# CoaxPress_SFP.net
KiCad netlist of a schematic drawn in Altium Designer
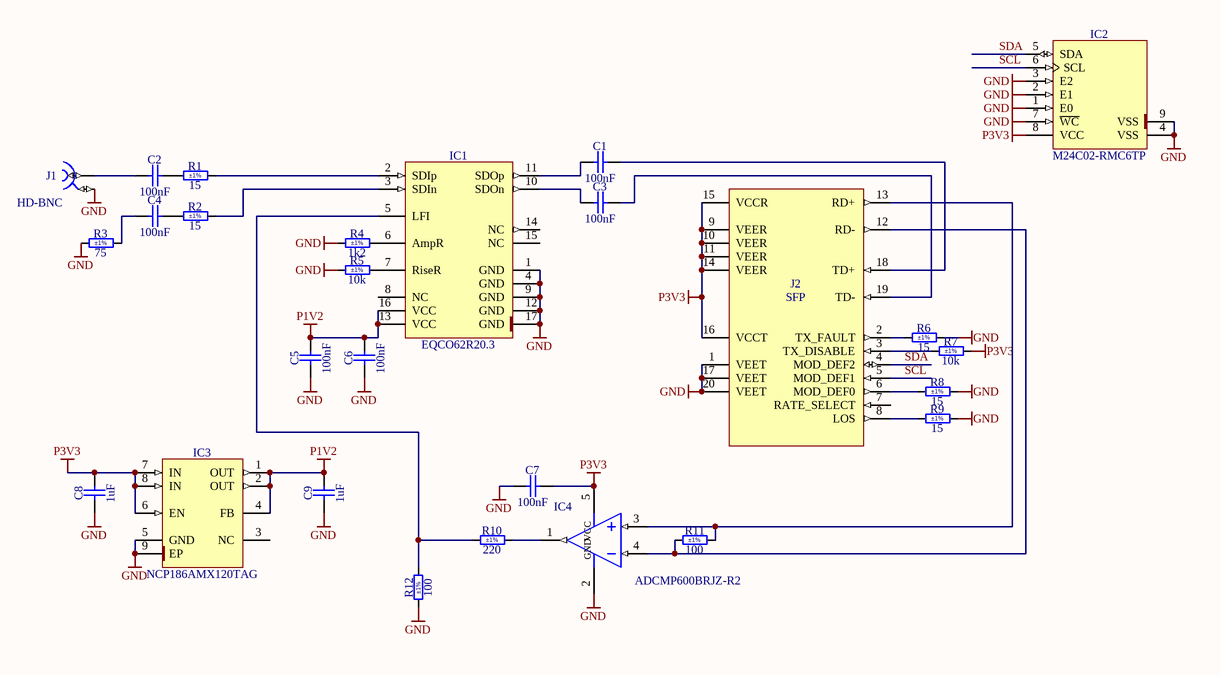
[diagram p0: CoaxPress_SFP.SchDoc]

(export (version "E")
  (design (tool "Eeschema 10.0.6"))
  (components
    (comp (ref "C1")
      (value "100nF")
      (footprint "CAPC1005X55N")
      (description "Non-polarised capacitor")
      (fields
        (field (name "PART NUMBER") "CC0402_100NF_16V_10%_X5R")
        (field (name "VOLTAGE") "16V")
        (field (name "AUTHOR") "CERN DEM JLC")
      )
      (libsource (lib "Capacitors") (part "Capacitor - non polarized"))
    )
    (comp (ref "C2")
      (value "100nF")
      (footprint "CAPC1005X55N")
      (description "Non-polarised capacitor")
      (fields
        (field (name "PART NUMBER") "CC0402_100NF_16V_10%_X5R")
        (field (name "VOLTAGE") "16V")
        (field (name "AUTHOR") "CERN DEM JLC")
      )
      (libsource (lib "Capacitors") (part "Capacitor - non polarized"))
    )
    (comp (ref "C3")
      (value "100nF")
      (footprint "CAPC1005X55N")
      (description "Non-polarised capacitor")
      (fields
        (field (name "PART NUMBER") "CC0402_100NF_16V_10%_X5R")
        (field (name "VOLTAGE") "16V")
        (field (name "AUTHOR") "CERN DEM JLC")
      )
      (libsource (lib "Capacitors") (part "Capacitor - non polarized"))
    )
    (comp (ref "C4")
      (value "100nF")
      (footprint "CAPC1005X55N")
      (description "Non-polarised capacitor")
      (fields
        (field (name "PART NUMBER") "CC0402_100NF_16V_10%_X5R")
        (field (name "VOLTAGE") "16V")
        (field (name "AUTHOR") "CERN DEM JLC")
      )
      (libsource (lib "Capacitors") (part "Capacitor - non polarized"))
    )
    (comp (ref "C5")
      (value "100nF")
      (footprint "CAPC1005X55N")
      (description "Non-polarised capacitor")
      (fields
        (field (name "PART NUMBER") "CC0402_100NF_16V_10%_X5R")
        (field (name "VOLTAGE") "16V")
        (field (name "AUTHOR") "CERN DEM JLC")
      )
      (libsource (lib "Capacitors") (part "Capacitor - non polarized"))
    )
    (comp (ref "C6")
      (value "100nF")
      (footprint "CAPC1005X55N")
      (description "Non-polarised capacitor")
      (fields
        (field (name "PART NUMBER") "CC0402_100NF_16V_10%_X5R")
        (field (name "VOLTAGE") "16V")
        (field (name "AUTHOR") "CERN DEM JLC")
      )
      (libsource (lib "Capacitors") (part "Capacitor - non polarized"))
    )
    (comp (ref "C7")
      (value "100nF")
      (footprint "CAPC1005X55N")
      (description "Non-polarised capacitor")
      (fields
        (field (name "PART NUMBER") "CC0402_100NF_16V_10%_X5R")
        (field (name "VOLTAGE") "16V")
        (field (name "AUTHOR") "CERN DEM JLC")
      )
      (libsource (lib "Capacitors") (part "Capacitor - non polarized"))
    )
    (comp (ref "C8")
      (value "1uF")
      (footprint "CAPC1005X55N")
      (description "Non-polarised capacitor")
      (fields
        (field (name "PART NUMBER") "CC0402_1UF_16V_10%_X5R")
        (field (name "VOLTAGE") "16V")
        (field (name "AUTHOR") "CERN DEM JLC")
      )
      (libsource (lib "Capacitors") (part "Capacitor - non polarized"))
    )
    (comp (ref "C9")
      (value "1uF")
      (footprint "CAPC1005X55N")
      (description "Non-polarised capacitor")
      (fields
        (field (name "PART NUMBER") "CC0402_1UF_16V_10%_X5R")
        (field (name "VOLTAGE") "16V")
        (field (name "AUTHOR") "CERN DEM JLC")
      )
      (libsource (lib "Capacitors") (part "Capacitor - non polarized"))
    )
    (comp (ref "IC1")
      (value "EQCO62R20.3")
      (footprint "QFN65P400X400X95-17N-S215")
      (description "6.25Gbps Asymmetric Coax Equalizer")
      (fields (field (name "MANUFACTURER") "MICROCHIP TECHNOLOGY") (field (name "AUTHOR") "CERN DEM JLC"))
      (libsource (lib "ICs And Semiconductors") (part "EQCO62R20"))
    )
    (comp (ref "IC2")
      (value "M24C02-RMC6TP")
      (footprint "SON50P300X200X60-9N-S160")
      (description "2-Kbit (256 x 8bit) Serial I2C Bus EEPROM")
      (fields (field (name "MANUFACTURER") "ST MICROELECTRONICS") (field (name "AUTHOR") "CERN DEM MR"))
      (libsource (lib "ICs And Semiconductors") (part "M24C02-RMC"))
    )
    (comp (ref "IC3")
      (value "NCP186AMX120TAG")
      (footprint "ONSEMI_CASE 711AS")
      (description "1A, LDO Regulator - Fast Transient Response Low Voltage")
      (fields
        (field (name "MANUFACTURER") "ON SEMICONDUCTOR")
        (field (name "MANUFACTURER PART NUMBER") "NCP186AMX120TA")
        (field (name "AUTHOR") "CERN DEM BC")
      )
      (libsource (lib "ICs And Semiconductors") (part "NCP186AMX"))
    )
    (comp (ref "IC4")
      (value "ADCMP600BRJZ-R2")
      (footprint "SOT95P280X145-5N")
      (description "Rail-to-Rail, Very Fast, 2.5 V to 5.5 V Single-Supply TTL/CMOS Comparator")
      (fields
        (field (name "MANUFACTURER") "ANALOG DEVICES")
        (field (name "MANUFACTURER PART NUMBER") "ADCMP600BRJ")
        (field (name "AUTHOR") "CERN DEM JLC")
      )
      (libsource (lib "ICs And Semiconductors") (part "ADCMP600"))
    )
    (comp (ref "J1")
      (value "HD-BNC")
      (footprint "AMPHENOL_34-1030-12G")
      (fields
        (field (name "PART NUMBER") "AMPHENOL_34-1030-12G")
        (field (name "MANUFACTURER") "AMPHENOL-RF")
        (field (name "MANUFACTURER PART NUMBER") "34-1030-12G")
        (field (name "AUTHOR") "CERN DEM JLC")
      )
      (libsource (lib "Connectors") (part "Coax_1Female_1Shield"))
    )
    (comp (ref "J2")
      (value "SFP")
      (footprint "SFP_PCB_EDGE")
      (description "20 Position SFP  Connector (Small Form-factor Pluggable)")
      (fields (field (name "PART NUMBER") "SFP_PCB_EDGE") (field (name "AUTHOR") "CERN DEM JLC"))
      (libsource (lib "Connectors") (part "SFPx1"))
    )
    (comp (ref "R1")
      (value "15")
      (footprint "RESC1005X40N")
      (description "Resistor - 1%")
      (fields
        (field (name "TOLERANCE") "±1%")
        (field (name "PART NUMBER") "R0402_15R_1%_0.0625W_100PPM")
        (field (name "POWER") "0.0625W")
        (field (name "AUTHOR") "CERN DEM JLC")
      )
      (libsource (lib "Resistors") (part "Resistor - 1%"))
    )
    (comp (ref "R2")
      (value "15")
      (footprint "RESC1005X40N")
      (description "Resistor - 1%")
      (fields
        (field (name "TOLERANCE") "±1%")
        (field (name "PART NUMBER") "R0402_15R_1%_0.0625W_100PPM")
        (field (name "POWER") "0.0625W")
        (field (name "AUTHOR") "CERN DEM JLC")
      )
      (libsource (lib "Resistors") (part "Resistor - 1%"))
    )
    (comp (ref "R3")
      (value "75")
      (footprint "RESC1005X40N")
      (description "Resistor - 1%")
      (fields
        (field (name "TOLERANCE") "±1%")
        (field (name "PART NUMBER") "R0402_75R_1%_0.0625W_100PPM")
        (field (name "POWER") "0.0625W")
        (field (name "AUTHOR") "CERN DEM JLC")
      )
      (libsource (lib "Resistors") (part "Resistor - 1%"))
    )
    (comp (ref "R4")
      (value "1k2")
      (footprint "RESC1005X40N")
      (description "Resistor - 1%")
      (fields
        (field (name "TOLERANCE") "±1%")
        (field (name "PART NUMBER") "R0402_1K2_1%_0.0625W_100PPM")
        (field (name "POWER") "0.0625W")
        (field (name "AUTHOR") "CERN DEM JLC")
      )
      (libsource (lib "Resistors") (part "Resistor - 1%"))
    )
    (comp (ref "R5")
      (value "10k")
      (footprint "RESC1005X40N")
      (description "Resistor - 1%")
      (fields
        (field (name "TOLERANCE") "±1%")
        (field (name "PART NUMBER") "R0402_10K_1%_0.0625W_100PPM")
        (field (name "POWER") "0.0625W")
        (field (name "AUTHOR") "CERN DEM JLC")
      )
      (libsource (lib "Resistors") (part "Resistor - 1%"))
    )
    (comp (ref "R6")
      (value "15")
      (footprint "RESC1005X40N")
      (description "Resistor - 1%")
      (fields
        (field (name "TOLERANCE") "±1%")
        (field (name "PART NUMBER") "R0402_15R_1%_0.0625W_100PPM")
        (field (name "POWER") "0.0625W")
        (field (name "AUTHOR") "CERN DEM JLC")
      )
      (libsource (lib "Resistors") (part "Resistor - 1%"))
    )
    (comp (ref "R7")
      (value "10k")
      (footprint "RESC1005X40N")
      (description "Resistor - 1%")
      (fields
        (field (name "TOLERANCE") "±1%")
        (field (name "PART NUMBER") "R0402_10K_1%_0.0625W_100PPM")
        (field (name "POWER") "0.0625W")
        (field (name "AUTHOR") "CERN DEM JLC")
      )
      (libsource (lib "Resistors") (part "Resistor - 1%"))
    )
    (comp (ref "R8")
      (value "15")
      (footprint "RESC1005X40N")
      (description "Resistor - 1%")
      (fields
        (field (name "TOLERANCE") "±1%")
        (field (name "PART NUMBER") "R0402_15R_1%_0.0625W_100PPM")
        (field (name "POWER") "0.0625W")
        (field (name "AUTHOR") "CERN DEM JLC")
      )
      (libsource (lib "Resistors") (part "Resistor - 1%"))
    )
    (comp (ref "R9")
      (value "15")
      (footprint "RESC1005X40N")
      (description "Resistor - 1%")
      (fields
        (field (name "TOLERANCE") "±1%")
        (field (name "PART NUMBER") "R0402_15R_1%_0.0625W_100PPM")
        (field (name "POWER") "0.0625W")
        (field (name "AUTHOR") "CERN DEM JLC")
      )
      (libsource (lib "Resistors") (part "Resistor - 1%"))
    )
    (comp (ref "R10")
      (value "220")
      (footprint "RESC1005X40N")
      (description "Resistor - 1%")
      (fields
        (field (name "TOLERANCE") "±1%")
        (field (name "PART NUMBER") "R0402_220R_1%_0.0625W_100PPM")
        (field (name "POWER") "0.0625W")
        (field (name "AUTHOR") "CERN DEM JLC")
      )
      (libsource (lib "Resistors") (part "Resistor - 1%"))
    )
    (comp (ref "R11")
      (value "100")
      (footprint "RESC1005X40N")
      (description "Resistor - 1%")
      (fields
        (field (name "TOLERANCE") "±1%")
        (field (name "PART NUMBER") "R0402_100R_1%_0.1W_100PPM")
        (field (name "POWER") "0.1W")
        (field (name "AUTHOR") "CERN DEM JLC")
      )
      (libsource (lib "Resistors") (part "Resistor - 1%"))
    )
    (comp (ref "R12")
      (value "100")
      (footprint "RESC1005X40N")
      (description "Resistor - 1%")
      (fields
        (field (name "TOLERANCE") "±1%")
        (field (name "PART NUMBER") "R0402_100R_1%_0.1W_100PPM")
        (field (name "POWER") "0.1W")
        (field (name "AUTHOR") "CERN DEM JLC")
      )
      (libsource (lib "Resistors") (part "Resistor - 1%"))
    )
  )
  (nets
    (net (code "1") (name "/SCL") (class "Default")
      (node (ref "IC2") (pin "6") (pinfunction "SCL_6") (pintype "input"))
      (node (ref "J2") (pin "5") (pinfunction "MOD_DEF1_5") (pintype "input"))
    )
    (net (code "2") (name "/SDA") (class "Default")
      (node (ref "IC2") (pin "5") (pinfunction "SDA_5") (pintype "bidirectional"))
      (node (ref "J2") (pin "4") (pinfunction "MOD_DEF2_4") (pintype "bidirectional"))
    )
    (net (code "3") (name "GND") (class "Default")
      (node (ref "C5") (pin "1") (pinfunction "1_1") (pintype "passive"))
      (node (ref "C6") (pin "1") (pinfunction "1_1") (pintype "passive"))
      (node (ref "C7") (pin "1") (pinfunction "1_1") (pintype "passive"))
      (node (ref "C8") (pin "1") (pinfunction "1_1") (pintype "passive"))
      (node (ref "C9") (pin "1") (pinfunction "1_1") (pintype "passive"))
      (node (ref "IC1") (pin "1") (pinfunction "GND_1") (pintype "power_in"))
      (node (ref "IC1") (pin "12") (pinfunction "GND_12") (pintype "power_in"))
      (node (ref "IC1") (pin "17") (pinfunction "GND_17") (pintype "power_in"))
      (node (ref "IC1") (pin "4") (pinfunction "GND_4") (pintype "power_in"))
      (node (ref "IC1") (pin "9") (pinfunction "GND_9") (pintype "power_in"))
      (node (ref "IC2") (pin "1") (pinfunction "E0_1") (pintype "input"))
      (node (ref "IC2") (pin "2") (pinfunction "E1_2") (pintype "input"))
      (node (ref "IC2") (pin "3") (pinfunction "E2_3") (pintype "input"))
      (node (ref "IC2") (pin "4") (pinfunction "VSS_4") (pintype "power_in"))
      (node (ref "IC2") (pin "7") (pinfunction "~{WC}_7") (pintype "input"))
      (node (ref "IC2") (pin "9") (pinfunction "VSS_9") (pintype "power_in"))
      (node (ref "IC3") (pin "5") (pinfunction "GND_5") (pintype "power_in"))
      (node (ref "IC3") (pin "9") (pinfunction "EP_9") (pintype "power_in"))
      (node (ref "IC4") (pin "2") (pinfunction "GND_2") (pintype "power_in"))
      (node (ref "J1") (pin "2") (pinfunction "2_2") (pintype "bidirectional"))
      (node (ref "J2") (pin "1") (pinfunction "VEET_1") (pintype "power_in"))
      (node (ref "J2") (pin "17") (pinfunction "VEET_17") (pintype "power_in"))
      (node (ref "J2") (pin "20") (pinfunction "VEET_20") (pintype "power_in"))
      (node (ref "R12") (pin "1") (pinfunction "1_1") (pintype "passive"))
      (node (ref "R3") (pin "1") (pinfunction "1_1") (pintype "passive"))
      (node (ref "R4") (pin "1") (pinfunction "1_1") (pintype "passive"))
      (node (ref "R5") (pin "1") (pinfunction "1_1") (pintype "passive"))
      (node (ref "R6") (pin "2") (pinfunction "2_2") (pintype "passive"))
      (node (ref "R8") (pin "2") (pinfunction "2_2") (pintype "passive"))
      (node (ref "R9") (pin "2") (pinfunction "2_2") (pintype "passive"))
    )
    (net (code "4") (name "Net-(C2-Pad1)") (class "Default")
      (node (ref "C2") (pin "1") (pinfunction "1_1") (pintype "passive"))
      (node (ref "J1") (pin "1") (pinfunction "1_1") (pintype "bidirectional"))
    )
    (net (code "5") (name "Net-(C2-Pad2)") (class "Default")
      (node (ref "C2") (pin "2") (pinfunction "2_2") (pintype "passive"))
      (node (ref "R1") (pin "1") (pinfunction "1_1") (pintype "passive"))
    )
    (net (code "6") (name "Net-(C4-Pad1)") (class "Default")
      (node (ref "C4") (pin "1") (pinfunction "1_1") (pintype "passive"))
      (node (ref "R3") (pin "2") (pinfunction "2_2") (pintype "passive"))
    )
    (net (code "7") (name "Net-(C4-Pad2)") (class "Default")
      (node (ref "C4") (pin "2") (pinfunction "2_2") (pintype "passive"))
      (node (ref "R2") (pin "1") (pinfunction "1_1") (pintype "passive"))
    )
    (net (code "8") (name "Net-(IC1-AmpR)") (class "Default")
      (node (ref "IC1") (pin "6") (pinfunction "AmpR_6") (pintype "passive"))
      (node (ref "R4") (pin "2") (pinfunction "2_2") (pintype "passive"))
    )
    (net (code "9") (name "Net-(IC1-LFI)") (class "Default")
      (node (ref "IC1") (pin "5") (pinfunction "LFI_5") (pintype "passive"))
      (node (ref "R10") (pin "1") (pinfunction "1_1") (pintype "passive"))
      (node (ref "R12") (pin "2") (pinfunction "2_2") (pintype "passive"))
    )
    (net (code "10") (name "Net-(IC1-RiseR)") (class "Default")
      (node (ref "IC1") (pin "7") (pinfunction "RiseR_7") (pintype "passive"))
      (node (ref "R5") (pin "2") (pinfunction "2_2") (pintype "passive"))
    )
    (net (code "11") (name "Net-(IC1-SDIn)") (class "Default")
      (node (ref "IC1") (pin "3") (pinfunction "SDIn_3") (pintype "input"))
      (node (ref "R2") (pin "2") (pinfunction "2_2") (pintype "passive"))
    )
    (net (code "12") (name "Net-(IC1-SDIp)") (class "Default")
      (node (ref "IC1") (pin "2") (pinfunction "SDIp_2") (pintype "input"))
      (node (ref "R1") (pin "2") (pinfunction "2_2") (pintype "passive"))
    )
    (net (code "13") (name "Net-(IC1-SDOn)") (class "Default")
      (node (ref "C3") (pin "1") (pinfunction "1_1") (pintype "passive"))
      (node (ref "IC1") (pin "10") (pinfunction "SDOn_10") (pintype "output"))
    )
    (net (code "14") (name "Net-(IC1-SDOp)") (class "Default")
      (node (ref "C1") (pin "1") (pinfunction "1_1") (pintype "passive"))
      (node (ref "IC1") (pin "11") (pinfunction "SDOp_11") (pintype "output"))
    )
    (net (code "15") (name "Net-(IC4-VN)") (class "Default")
      (node (ref "IC4") (pin "4") (pinfunction "VN_4") (pintype "input"))
      (node (ref "J2") (pin "12") (pinfunction "RD-_12") (pintype "output"))
      (node (ref "R11") (pin "1") (pinfunction "1_1") (pintype "passive"))
    )
    (net (code "16") (name "Net-(IC4-VP)") (class "Default")
      (node (ref "IC4") (pin "3") (pinfunction "VP_3") (pintype "input"))
      (node (ref "J2") (pin "13") (pinfunction "RD+_13") (pintype "output"))
      (node (ref "R11") (pin "2") (pinfunction "2_2") (pintype "passive"))
    )
    (net (code "17") (name "Net-(IC4-q)") (class "Default")
      (node (ref "IC4") (pin "1") (pinfunction "q_1") (pintype "output"))
      (node (ref "R10") (pin "2") (pinfunction "2_2") (pintype "passive"))
    )
    (net (code "18") (name "Net-(J2-LOS)") (class "Default")
      (node (ref "J2") (pin "8") (pinfunction "LOS_8") (pintype "output"))
      (node (ref "R9") (pin "1") (pinfunction "1_1") (pintype "passive"))
    )
    (net (code "19") (name "Net-(J2-MOD_DEF0)") (class "Default")
      (node (ref "J2") (pin "6") (pinfunction "MOD_DEF0_6") (pintype "output"))
      (node (ref "R8") (pin "1") (pinfunction "1_1") (pintype "passive"))
    )
    (net (code "20") (name "Net-(J2-TD+)") (class "Default")
      (node (ref "C1") (pin "2") (pinfunction "2_2") (pintype "passive"))
      (node (ref "J2") (pin "18") (pinfunction "TD+_18") (pintype "input"))
    )
    (net (code "21") (name "Net-(J2-TD-)") (class "Default")
      (node (ref "C3") (pin "2") (pinfunction "2_2") (pintype "passive"))
      (node (ref "J2") (pin "19") (pinfunction "TD-_19") (pintype "input"))
    )
    (net (code "22") (name "Net-(J2-TX_DISABLE)") (class "Default")
      (node (ref "J2") (pin "3") (pinfunction "TX_DISABLE_3") (pintype "input"))
      (node (ref "R7") (pin "1") (pinfunction "1_1") (pintype "passive"))
    )
    (net (code "23") (name "Net-(J2-TX_FAULT)") (class "Default")
      (node (ref "J2") (pin "2") (pinfunction "TX_FAULT_2") (pintype "output"))
      (node (ref "R6") (pin "1") (pinfunction "1_1") (pintype "passive"))
    )
    (net (code "24") (name "P1V2") (class "Default")
      (node (ref "C5") (pin "2") (pinfunction "2_2") (pintype "passive"))
      (node (ref "C6") (pin "2") (pinfunction "2_2") (pintype "passive"))
      (node (ref "C9") (pin "2") (pinfunction "2_2") (pintype "passive"))
      (node (ref "IC1") (pin "13") (pinfunction "VCC_13") (pintype "power_in"))
      (node (ref "IC1") (pin "16") (pinfunction "VCC_16") (pintype "passive"))
      (node (ref "IC3") (pin "1") (pinfunction "OUT_1") (pintype "output"))
      (node (ref "IC3") (pin "2") (pinfunction "OUT_2") (pintype "output"))
      (node (ref "IC3") (pin "4") (pinfunction "FB_4") (pintype "open_collector"))
    )
    (net (code "25") (name "P3V3") (class "Default")
      (node (ref "C7") (pin "2") (pinfunction "2_2") (pintype "passive"))
      (node (ref "C8") (pin "2") (pinfunction "2_2") (pintype "passive"))
      (node (ref "IC2") (pin "8") (pinfunction "VCC_8") (pintype "power_in"))
      (node (ref "IC3") (pin "6") (pinfunction "EN_6") (pintype "input"))
      (node (ref "IC3") (pin "7") (pinfunction "IN_7") (pintype "input"))
      (node (ref "IC3") (pin "8") (pinfunction "IN_8") (pintype "input"))
      (node (ref "IC4") (pin "5") (pinfunction "VCC_5") (pintype "power_in"))
      (node (ref "J2") (pin "10") (pinfunction "VEER_10") (pintype "power_in"))
      (node (ref "J2") (pin "11") (pinfunction "VEER_11") (pintype "power_in"))
      (node (ref "J2") (pin "14") (pinfunction "VEER_14") (pintype "power_in"))
      (node (ref "J2") (pin "15") (pinfunction "VCCR_15") (pintype "power_in"))
      (node (ref "J2") (pin "16") (pinfunction "VCCT_16") (pintype "power_in"))
      (node (ref "J2") (pin "9") (pinfunction "VEER_9") (pintype "power_in"))
      (node (ref "R7") (pin "2") (pinfunction "2_2") (pintype "passive"))
    )
    (net (code "26") (name "unconnected-(IC1-NC-Pad8)") (class "Default")
      (node (ref "IC1") (pin "8") (pinfunction "NC_8") (pintype "passive"))
    )
    (net (code "27") (name "unconnected-(IC1-NC-Pad14)") (class "Default")
      (node (ref "IC1") (pin "14") (pinfunction "NC_14") (pintype "output"))
    )
    (net (code "28") (name "unconnected-(IC1-NC-Pad15)") (class "Default")
      (node (ref "IC1") (pin "15") (pinfunction "NC_15") (pintype "passive"))
    )
    (net (code "29") (name "unconnected-(IC3-NC-Pad3)") (class "Default")
      (node (ref "IC3") (pin "3") (pinfunction "NC_3") (pintype "passive"))
    )
    (net (code "30") (name "unconnected-(J2-RATE_SELECT-Pad7)") (class "Default")
      (node (ref "J2") (pin "7") (pinfunction "RATE_SELECT_7") (pintype "input"))
    )
  )
)
